# Safety_LightsSch.net
KiCad netlist of a schematic drawn in Altium Designer
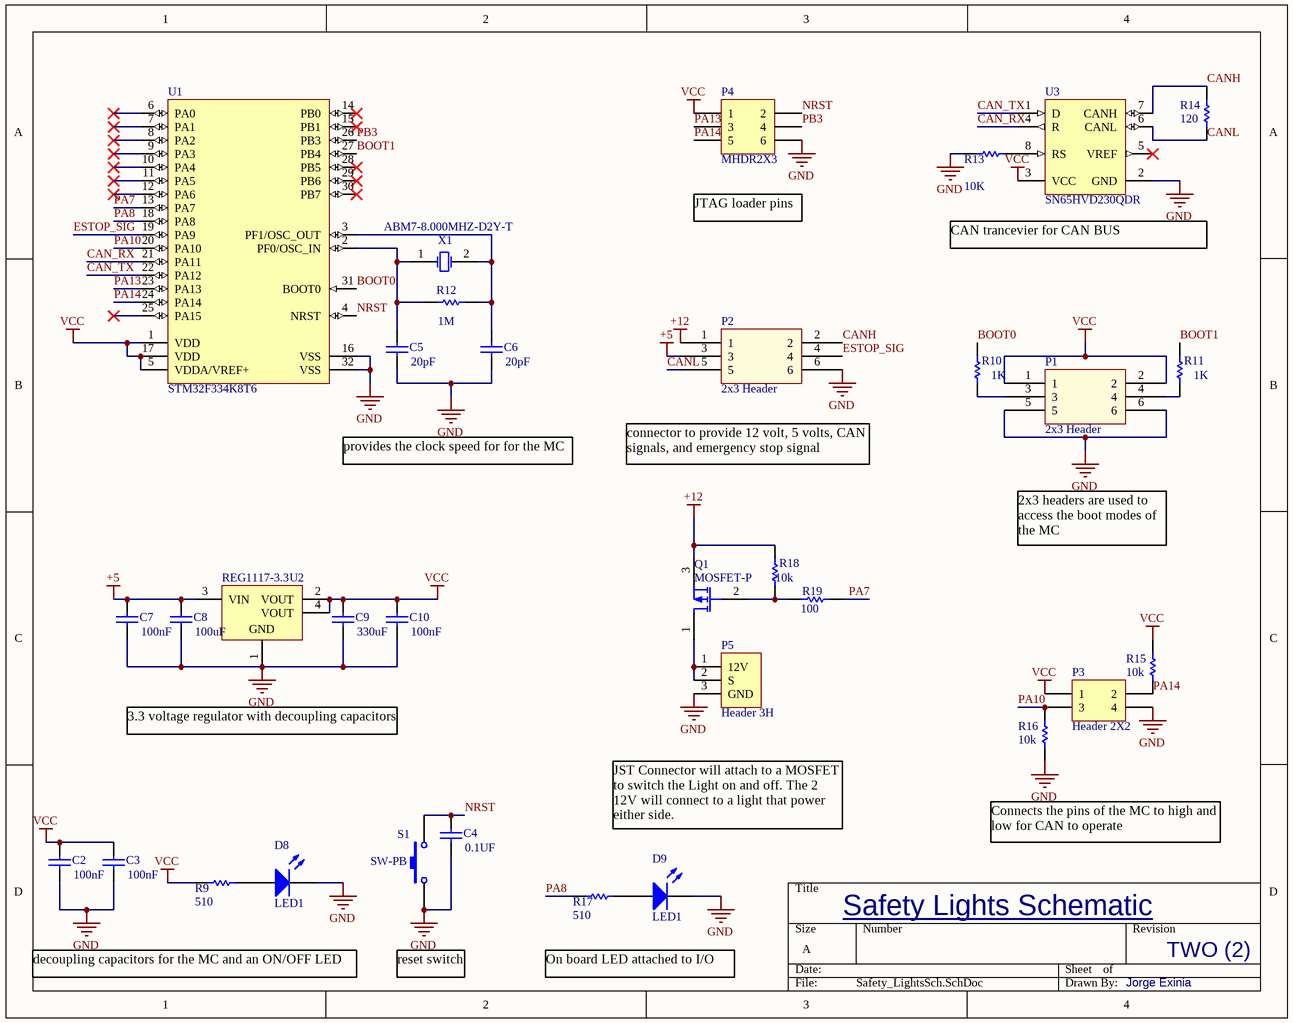
[diagram p0: Safety_LightsSch.SchDoc]

(export (version "E")
  (design (tool "Eeschema 10.0.6"))
  (components
    (comp (ref "C2")
      (value "100nF")
      (footprint "6-0805_L")
      (description "Capacitor")
      (fields (field (name "Comment") "Cap") (field (name "PUBLISHER") "Altium Limited"))
      (libsource (lib "Miscellaneous Devices") (part "Cap"))
    )
    (comp (ref "C3")
      (value "100nF")
      (footprint "6-0805_L")
      (description "Capacitor")
      (fields (field (name "Comment") "Cap") (field (name "PUBLISHER") "Altium Limited"))
      (libsource (lib "Miscellaneous Devices") (part "Cap"))
    )
    (comp (ref "C4")
      (value "0.1UF")
      (footprint "6-0805_L")
      (description "Capacitor")
      (fields (field (name "Comment") "Cap") (field (name "PUBLISHER") "Altium Limited"))
      (libsource (lib "Miscellaneous Devices") (part "Cap"))
    )
    (comp (ref "C5")
      (value "20pF")
      (footprint "6-0805_L")
      (description "Capacitor")
      (fields (field (name "Comment") "Cap") (field (name "PUBLISHER") "Altium Limited"))
      (libsource (lib "Miscellaneous Devices") (part "Cap"))
    )
    (comp (ref "C6")
      (value "20pF")
      (footprint "6-0805_L")
      (description "Capacitor")
      (fields (field (name "Comment") "Cap") (field (name "PUBLISHER") "Altium Limited"))
      (libsource (lib "Miscellaneous Devices") (part "Cap"))
    )
    (comp (ref "C7")
      (value "100nF")
      (footprint "6-0805_L")
      (description "Capacitor")
      (fields (field (name "Comment") "Cap") (field (name "PUBLISHER") "Altium Limited"))
      (libsource (lib "Miscellaneous Devices") (part "Cap"))
    )
    (comp (ref "C8")
      (value "100uF")
      (footprint "6-0805_L")
      (description "Capacitor")
      (fields (field (name "Comment") "Cap") (field (name "PUBLISHER") "Altium Limited"))
      (libsource (lib "Miscellaneous Devices") (part "Cap"))
    )
    (comp (ref "C9")
      (value "330uF")
      (footprint "6-0805_L")
      (description "Capacitor")
      (fields (field (name "Comment") "Cap") (field (name "PUBLISHER") "Altium Limited"))
      (libsource (lib "Miscellaneous Devices") (part "Cap"))
    )
    (comp (ref "C10")
      (value "100nF")
      (footprint "6-0805_L")
      (description "Capacitor")
      (fields (field (name "Comment") "Cap") (field (name "PUBLISHER") "Altium Limited"))
      (libsource (lib "Miscellaneous Devices") (part "Cap"))
    )
    (comp (ref "D8")
      (value "LED1")
      (footprint "6-0805_L")
      (description "Typical RED GaAs LED")
      (fields (field (name "PUBLISHER") "Altium Limited"))
      (libsource (lib "Miscellaneous Devices") (part "LED1"))
    )
    (comp (ref "D9")
      (value "LED1")
      (footprint "6-0805_L")
      (description "Typical RED GaAs LED")
      (fields (field (name "PUBLISHER") "Altium Limited"))
      (libsource (lib "Miscellaneous Devices") (part "LED1"))
    )
    (comp (ref "P1")
      (value "2x3 Header")
      (footprint "HDR2X3")
      (libsource (lib "Schlib1") (part "2x3 Header"))
    )
    (comp (ref "P2")
      (value "2x3 Header")
      (footprint "Molex Connector")
      (libsource (lib "Schlib1") (part "2x3 Header"))
    )
    (comp (ref "P3")
      (value "Header 2X2")
      (footprint "HDR2X2")
      (description "Header, 2-Pin, Dual row")
      (fields (field (name "PUBLISHER") "Altium Limited"))
      (libsource (lib "Miscellaneous Connectors") (part "Header 2X2"))
    )
    (comp (ref "P4")
      (value "MHDR2X3")
      (footprint "HDR2X3")
      (description "Header, 3-Pin, Dual row")
      (fields (field (name "PUBLISHER") "Altium Limited"))
      (libsource (lib "Miscellaneous Connectors") (part "MHDR2X3"))
    )
    (comp (ref "P5")
      (value "Header 3H")
      (footprint "HDR1X3")
      (description "Header, 3-Pin, Right Angle")
      (fields (field (name "PUBLISHER") "Altium Limited"))
      (libsource (lib "Miscellaneous Connectors") (part "Header 3H"))
    )
    (comp (ref "Q1")
      (value "MOSFET-P")
      (footprint "E3")
      (description "P-Channel MOSFET")
      (fields (field (name "PUBLISHER") "Altium Limited"))
      (libsource (lib "Miscellaneous Devices") (part "MOSFET-P"))
    )
    (comp (ref "R9")
      (value "510")
      (footprint "1608[0603]")
      (description "Resistor")
      (fields (field (name "Comment") "Res1") (field (name "PUBLISHER") "Altium Limited"))
      (libsource (lib "Miscellaneous Devices") (part "Res1"))
    )
    (comp (ref "R10")
      (value "1K")
      (footprint "1608[0603]")
      (description "Resistor")
      (fields (field (name "Comment") "Res1") (field (name "PUBLISHER") "Altium Limited"))
      (libsource (lib "Miscellaneous Devices") (part "Res1"))
    )
    (comp (ref "R11")
      (value "1K")
      (footprint "1608[0603]")
      (description "Resistor")
      (fields (field (name "Comment") "Res1") (field (name "PUBLISHER") "Altium Limited"))
      (libsource (lib "Miscellaneous Devices") (part "Res1"))
    )
    (comp (ref "R12")
      (value "1M")
      (footprint "1608[0603]")
      (description "Resistor")
      (fields (field (name "Comment") "Res1") (field (name "PUBLISHER") "Altium Limited"))
      (libsource (lib "Miscellaneous Devices") (part "Res1"))
    )
    (comp (ref "R13")
      (value "10K")
      (footprint "1608[0603]")
      (description "Resistor")
      (fields (field (name "Comment") "Res1") (field (name "PUBLISHER") "Altium Limited"))
      (libsource (lib "Miscellaneous Devices") (part "Res1"))
    )
    (comp (ref "R14")
      (value "120")
      (footprint "1608[0603]")
      (description "Resistor")
      (fields (field (name "Comment") "Res1") (field (name "PUBLISHER") "Altium Limited"))
      (libsource (lib "Miscellaneous Devices") (part "Res1"))
    )
    (comp (ref "R15")
      (value "10k")
      (footprint "1608[0603]")
      (description "Resistor")
      (fields (field (name "Comment") "Res1") (field (name "PUBLISHER") "Altium Limited"))
      (libsource (lib "Miscellaneous Devices") (part "Res1"))
    )
    (comp (ref "R16")
      (value "10k")
      (footprint "1608[0603]")
      (description "Resistor")
      (fields (field (name "Comment") "Res1") (field (name "PUBLISHER") "Altium Limited"))
      (libsource (lib "Miscellaneous Devices") (part "Res1"))
    )
    (comp (ref "R17")
      (value "510")
      (footprint "1608[0603]")
      (description "Resistor")
      (fields (field (name "Comment") "Res1") (field (name "PUBLISHER") "Altium Limited"))
      (libsource (lib "Miscellaneous Devices") (part "Res1"))
    )
    (comp (ref "R18")
      (value "10k")
      (footprint "1608[0603]")
      (description "Resistor")
      (fields (field (name "Comment") "Res1") (field (name "PUBLISHER") "Altium Limited"))
      (libsource (lib "Miscellaneous Devices") (part "Res1"))
    )
    (comp (ref "R19")
      (value "100")
      (footprint "1608[0603]")
      (description "Resistor")
      (fields (field (name "Comment") "Res1") (field (name "PUBLISHER") "Altium Limited"))
      (libsource (lib "Miscellaneous Devices") (part "Res1"))
    )
    (comp (ref "S1")
      (value "SW-PB")
      (footprint "Push Switch 3x6x2.5")
      (description "Switch")
      (fields (field (name "PUBLISHER") "Altium Limited"))
      (libsource (lib "Miscellaneous Devices") (part "SW-PB"))
    )
    (comp (ref "U1")
      (value "STM32F334K8T6")
      (footprint "STM-LQFP32_M")
      (libsource (lib "Altium Content Vault") (part "MC-ARM-STM32F334-LQFP32"))
    )
    (comp (ref "U2")
      (value "REG1117-3.3")
      (footprint "DCY0004A_M")
      (fields (field (name "MANUFACTURER") "Texas Instruments"))
      (libsource (lib "Altium Content Vault") (part "TI-REG1117-XXXX"))
    )
    (comp (ref "U3")
      (value "SN65HVD230QDR")
      (footprint "D0008A_L")
      (fields (field (name "MANUFACTURER") "Texas Instruments"))
      (libsource (lib "Altium Content Vault") (part "TI-SN65HVD230Q-SOIC_D-8"))
    )
    (comp (ref "X1")
      (value "ABM7-8.000MHZ-D2Y-T")
      (footprint "ABRA-ABM7-2_V")
      (description "Microprocessor Crystal, 8 MHz, 18 PF, -40 to 85 degC, 2-Pin SMD, RoHS, Tape and Reel")
      (fields (field (name "MANUFACTURER") "Abracon"))
      (libsource (lib "Altium Content Vault") (part "XTAL_1-2-2"))
    )
  )
  (nets
    (net (code "1") (name "+5") (class "Default")
      (node (ref "C7") (pin "2") (pinfunction "2_2") (pintype "passive"))
      (node (ref "C8") (pin "2") (pinfunction "2_2") (pintype "passive"))
      (node (ref "P2") (pin "3") (pinfunction "3_3") (pintype "passive"))
      (node (ref "U2") (pin "3") (pinfunction "VIN_3") (pintype "power_in"))
    )
    (net (code "2") (name "+12") (class "Default")
      (node (ref "P2") (pin "1") (pinfunction "1_1") (pintype "passive"))
      (node (ref "Q1") (pin "3") (pinfunction "S_3") (pintype "passive"))
      (node (ref "R18") (pin "2") (pinfunction "2_2") (pintype "passive"))
    )
    (net (code "3") (name "/BOOT0") (class "Default")
      (node (ref "R10") (pin "2") (pinfunction "2_2") (pintype "passive"))
      (node (ref "U1") (pin "31") (pinfunction "BOOT0_31") (pintype "input"))
    )
    (net (code "4") (name "/BOOT1") (class "Default")
      (node (ref "R11") (pin "2") (pinfunction "2_2") (pintype "passive"))
      (node (ref "U1") (pin "27") (pinfunction "PB4_27") (pintype "bidirectional"))
    )
    (net (code "5") (name "/CANH") (class "Default")
      (node (ref "P2") (pin "2") (pinfunction "2_2") (pintype "passive"))
      (node (ref "R14") (pin "2") (pinfunction "2_2") (pintype "passive"))
      (node (ref "U3") (pin "7") (pinfunction "CANH_7") (pintype "bidirectional"))
    )
    (net (code "6") (name "/CANL") (class "Default")
      (node (ref "P2") (pin "5") (pinfunction "5_5") (pintype "passive"))
      (node (ref "R14") (pin "1") (pinfunction "1_1") (pintype "passive"))
      (node (ref "U3") (pin "6") (pinfunction "CANL_6") (pintype "bidirectional"))
    )
    (net (code "7") (name "/CAN_RX") (class "Default")
      (node (ref "U1") (pin "21") (pinfunction "PA11_21") (pintype "bidirectional"))
      (node (ref "U3") (pin "4") (pinfunction "R_4") (pintype "output"))
    )
    (net (code "8") (name "/CAN_TX") (class "Default")
      (node (ref "U1") (pin "22") (pinfunction "PA12_22") (pintype "bidirectional"))
      (node (ref "U3") (pin "1") (pinfunction "D_1") (pintype "input"))
    )
    (net (code "9") (name "/ESTOP_SIG") (class "Default")
      (node (ref "P2") (pin "4") (pinfunction "4_4") (pintype "passive"))
      (node (ref "U1") (pin "19") (pinfunction "PA9_19") (pintype "bidirectional"))
    )
    (net (code "10") (name "/NRST") (class "Default")
      (node (ref "C4") (pin "2") (pinfunction "2_2") (pintype "passive"))
      (node (ref "P4") (pin "2") (pinfunction "2_2") (pintype "passive"))
      (node (ref "S1") (pin "2") (pinfunction "2_2") (pintype "passive"))
      (node (ref "U1") (pin "4") (pinfunction "NRST_4") (pintype "bidirectional"))
    )
    (net (code "11") (name "/PA7") (class "Default")
      (node (ref "R19") (pin "2") (pinfunction "2_2") (pintype "passive"))
      (node (ref "U1") (pin "13") (pinfunction "PA7_13") (pintype "bidirectional"))
    )
    (net (code "12") (name "/PA8") (class "Default")
      (node (ref "R17") (pin "1") (pinfunction "1_1") (pintype "passive"))
      (node (ref "U1") (pin "18") (pinfunction "PA8_18") (pintype "bidirectional"))
    )
    (net (code "13") (name "/PA10") (class "Default")
      (node (ref "P3") (pin "3") (pinfunction "3_3") (pintype "passive"))
      (node (ref "R16") (pin "2") (pinfunction "2_2") (pintype "passive"))
      (node (ref "U1") (pin "20") (pinfunction "PA10_20") (pintype "bidirectional"))
    )
    (net (code "14") (name "/PA13") (class "Default")
      (node (ref "P4") (pin "3") (pinfunction "3_3") (pintype "passive"))
      (node (ref "U1") (pin "23") (pinfunction "PA13_23") (pintype "bidirectional"))
    )
    (net (code "15") (name "/PA14") (class "Default")
      (node (ref "P3") (pin "2") (pinfunction "2_2") (pintype "passive"))
      (node (ref "P4") (pin "5") (pinfunction "5_5") (pintype "passive"))
      (node (ref "R15") (pin "1") (pinfunction "1_1") (pintype "passive"))
      (node (ref "U1") (pin "24") (pinfunction "PA14_24") (pintype "bidirectional"))
    )
    (net (code "16") (name "/PB3") (class "Default")
      (node (ref "P4") (pin "4") (pinfunction "4_4") (pintype "passive"))
      (node (ref "U1") (pin "26") (pinfunction "PB3_26") (pintype "bidirectional"))
    )
    (net (code "17") (name "GND") (class "Default")
      (node (ref "C10") (pin "1") (pinfunction "1_1") (pintype "passive"))
      (node (ref "C2") (pin "1") (pinfunction "1_1") (pintype "passive"))
      (node (ref "C3") (pin "1") (pinfunction "1_1") (pintype "passive"))
      (node (ref "C4") (pin "1") (pinfunction "1_1") (pintype "passive"))
      (node (ref "C5") (pin "2") (pinfunction "2_2") (pintype "passive"))
      (node (ref "C6") (pin "2") (pinfunction "2_2") (pintype "passive"))
      (node (ref "C7") (pin "1") (pinfunction "1_1") (pintype "passive"))
      (node (ref "C8") (pin "1") (pinfunction "1_1") (pintype "passive"))
      (node (ref "C9") (pin "1") (pinfunction "1_1") (pintype "passive"))
      (node (ref "D8") (pin "2") (pinfunction "K_2") (pintype "passive"))
      (node (ref "D9") (pin "2") (pinfunction "K_2") (pintype "passive"))
      (node (ref "P1") (pin "5") (pinfunction "5_5") (pintype "passive"))
      (node (ref "P1") (pin "6") (pinfunction "6_6") (pintype "passive"))
      (node (ref "P2") (pin "6") (pinfunction "6_6") (pintype "passive"))
      (node (ref "P3") (pin "4") (pinfunction "4_4") (pintype "passive"))
      (node (ref "P4") (pin "6") (pinfunction "6_6") (pintype "passive"))
      (node (ref "P5") (pin "3") (pinfunction "GND_3") (pintype "passive"))
      (node (ref "R13") (pin "1") (pinfunction "1_1") (pintype "passive"))
      (node (ref "R16") (pin "1") (pinfunction "1_1") (pintype "passive"))
      (node (ref "S1") (pin "1") (pinfunction "1_1") (pintype "passive"))
      (node (ref "U1") (pin "16") (pinfunction "VSS_16") (pintype "power_in"))
      (node (ref "U1") (pin "32") (pinfunction "VSS_32") (pintype "power_in"))
      (node (ref "U2") (pin "1") (pinfunction "GND_1") (pintype "power_in"))
      (node (ref "U3") (pin "2") (pinfunction "GND_2") (pintype "power_in"))
    )
    (net (code "18") (name "Net-(D8-A)") (class "Default")
      (node (ref "D8") (pin "1") (pinfunction "A_1") (pintype "passive"))
      (node (ref "R9") (pin "2") (pinfunction "2_2") (pintype "passive"))
    )
    (net (code "19") (name "Net-(D9-A)") (class "Default")
      (node (ref "D9") (pin "1") (pinfunction "A_1") (pintype "passive"))
      (node (ref "R17") (pin "2") (pinfunction "2_2") (pintype "passive"))
    )
    (net (code "20") (name "Net-(P1-Pad3)") (class "Default")
      (node (ref "P1") (pin "3") (pinfunction "3_3") (pintype "passive"))
      (node (ref "R10") (pin "1") (pinfunction "1_1") (pintype "passive"))
    )
    (net (code "21") (name "Net-(P1-Pad4)") (class "Default")
      (node (ref "P1") (pin "4") (pinfunction "4_4") (pintype "passive"))
      (node (ref "R11") (pin "1") (pinfunction "1_1") (pintype "passive"))
    )
    (net (code "22") (name "Net-(P5-12V)") (class "Default")
      (node (ref "P5") (pin "1") (pinfunction "12V_1") (pintype "passive"))
      (node (ref "P5") (pin "2") (pinfunction "S_2") (pintype "passive"))
      (node (ref "Q1") (pin "1") (pinfunction "D_1") (pintype "passive"))
    )
    (net (code "23") (name "Net-(Q1-G)") (class "Default")
      (node (ref "Q1") (pin "2") (pinfunction "G_2") (pintype "passive"))
      (node (ref "R18") (pin "1") (pinfunction "1_1") (pintype "passive"))
      (node (ref "R19") (pin "1") (pinfunction "1_1") (pintype "passive"))
    )
    (net (code "24") (name "Net-(U1-PF0{slash}OSC_IN)") (class "Default")
      (node (ref "C5") (pin "1") (pinfunction "1_1") (pintype "passive"))
      (node (ref "R12") (pin "1") (pinfunction "1_1") (pintype "passive"))
      (node (ref "U1") (pin "2") (pinfunction "PF0/OSC_IN_2") (pintype "bidirectional"))
      (node (ref "X1") (pin "1") (pinfunction "X1_1") (pintype "passive"))
    )
    (net (code "25") (name "Net-(U1-PF1{slash}OSC_OUT)") (class "Default")
      (node (ref "C6") (pin "1") (pinfunction "1_1") (pintype "passive"))
      (node (ref "R12") (pin "2") (pinfunction "2_2") (pintype "passive"))
      (node (ref "U1") (pin "3") (pinfunction "PF1/OSC_OUT_3") (pintype "bidirectional"))
      (node (ref "X1") (pin "2") (pinfunction "X2_2") (pintype "passive"))
    )
    (net (code "26") (name "Net-(U3-RS)") (class "Default")
      (node (ref "R13") (pin "2") (pinfunction "2_2") (pintype "passive"))
      (node (ref "U3") (pin "8") (pinfunction "RS_8") (pintype "input"))
    )
    (net (code "27") (name "VCC") (class "Default")
      (node (ref "C10") (pin "2") (pinfunction "2_2") (pintype "passive"))
      (node (ref "C2") (pin "2") (pinfunction "2_2") (pintype "passive"))
      (node (ref "C3") (pin "2") (pinfunction "2_2") (pintype "passive"))
      (node (ref "C9") (pin "2") (pinfunction "2_2") (pintype "passive"))
      (node (ref "P1") (pin "1") (pinfunction "1_1") (pintype "passive"))
      (node (ref "P1") (pin "2") (pinfunction "2_2") (pintype "passive"))
      (node (ref "P3") (pin "1") (pinfunction "1_1") (pintype "passive"))
      (node (ref "P4") (pin "1") (pinfunction "1_1") (pintype "passive"))
      (node (ref "R15") (pin "2") (pinfunction "2_2") (pintype "passive"))
      (node (ref "R9") (pin "1") (pinfunction "1_1") (pintype "passive"))
      (node (ref "U1") (pin "1") (pinfunction "VDD_1") (pintype "power_in"))
      (node (ref "U1") (pin "17") (pinfunction "VDD_17") (pintype "power_in"))
      (node (ref "U1") (pin "5") (pinfunction "VDDA/VREF+_5") (pintype "power_in"))
      (node (ref "U2") (pin "2") (pinfunction "VOUT_2") (pintype "power_in"))
      (node (ref "U2") (pin "4") (pinfunction "VOUT_4") (pintype "power_in"))
      (node (ref "U3") (pin "3") (pinfunction "VCC_3") (pintype "power_in"))
    )
    (net (code "28") (name "unconnected-(U1-PA0-Pad6)") (class "Default")
      (node (ref "U1") (pin "6") (pinfunction "PA0_6") (pintype "bidirectional+no_connect"))
    )
    (net (code "29") (name "unconnected-(U1-PA1-Pad7)") (class "Default")
      (node (ref "U1") (pin "7") (pinfunction "PA1_7") (pintype "bidirectional+no_connect"))
    )
    (net (code "30") (name "unconnected-(U1-PA2-Pad8)") (class "Default")
      (node (ref "U1") (pin "8") (pinfunction "PA2_8") (pintype "bidirectional+no_connect"))
    )
    (net (code "31") (name "unconnected-(U1-PA3-Pad9)") (class "Default")
      (node (ref "U1") (pin "9") (pinfunction "PA3_9") (pintype "bidirectional+no_connect"))
    )
    (net (code "32") (name "unconnected-(U1-PA4-Pad10)") (class "Default")
      (node (ref "U1") (pin "10") (pinfunction "PA4_10") (pintype "bidirectional+no_connect"))
    )
    (net (code "33") (name "unconnected-(U1-PA5-Pad11)") (class "Default")
      (node (ref "U1") (pin "11") (pinfunction "PA5_11") (pintype "bidirectional+no_connect"))
    )
    (net (code "34") (name "unconnected-(U1-PA6-Pad12)") (class "Default")
      (node (ref "U1") (pin "12") (pinfunction "PA6_12") (pintype "bidirectional+no_connect"))
    )
    (net (code "35") (name "unconnected-(U1-PA15-Pad25)") (class "Default")
      (node (ref "U1") (pin "25") (pinfunction "PA15_25") (pintype "bidirectional+no_connect"))
    )
    (net (code "36") (name "unconnected-(U1-PB0-Pad14)") (class "Default")
      (node (ref "U1") (pin "14") (pinfunction "PB0_14") (pintype "bidirectional+no_connect"))
    )
    (net (code "37") (name "unconnected-(U1-PB1-Pad15)") (class "Default")
      (node (ref "U1") (pin "15") (pinfunction "PB1_15") (pintype "bidirectional+no_connect"))
    )
    (net (code "38") (name "unconnected-(U1-PB5-Pad28)") (class "Default")
      (node (ref "U1") (pin "28") (pinfunction "PB5_28") (pintype "bidirectional+no_connect"))
    )
    (net (code "39") (name "unconnected-(U1-PB6-Pad29)") (class "Default")
      (node (ref "U1") (pin "29") (pinfunction "PB6_29") (pintype "bidirectional+no_connect"))
    )
    (net (code "40") (name "unconnected-(U1-PB7-Pad30)") (class "Default")
      (node (ref "U1") (pin "30") (pinfunction "PB7_30") (pintype "bidirectional+no_connect"))
    )
    (net (code "41") (name "unconnected-(U3-VREF-Pad5)") (class "Default")
      (node (ref "U3") (pin "5") (pinfunction "VREF_5") (pintype "output+no_connect"))
    )
  )
)
